# untitled.net
KiCad netlist of a schematic drawn in EAGLE
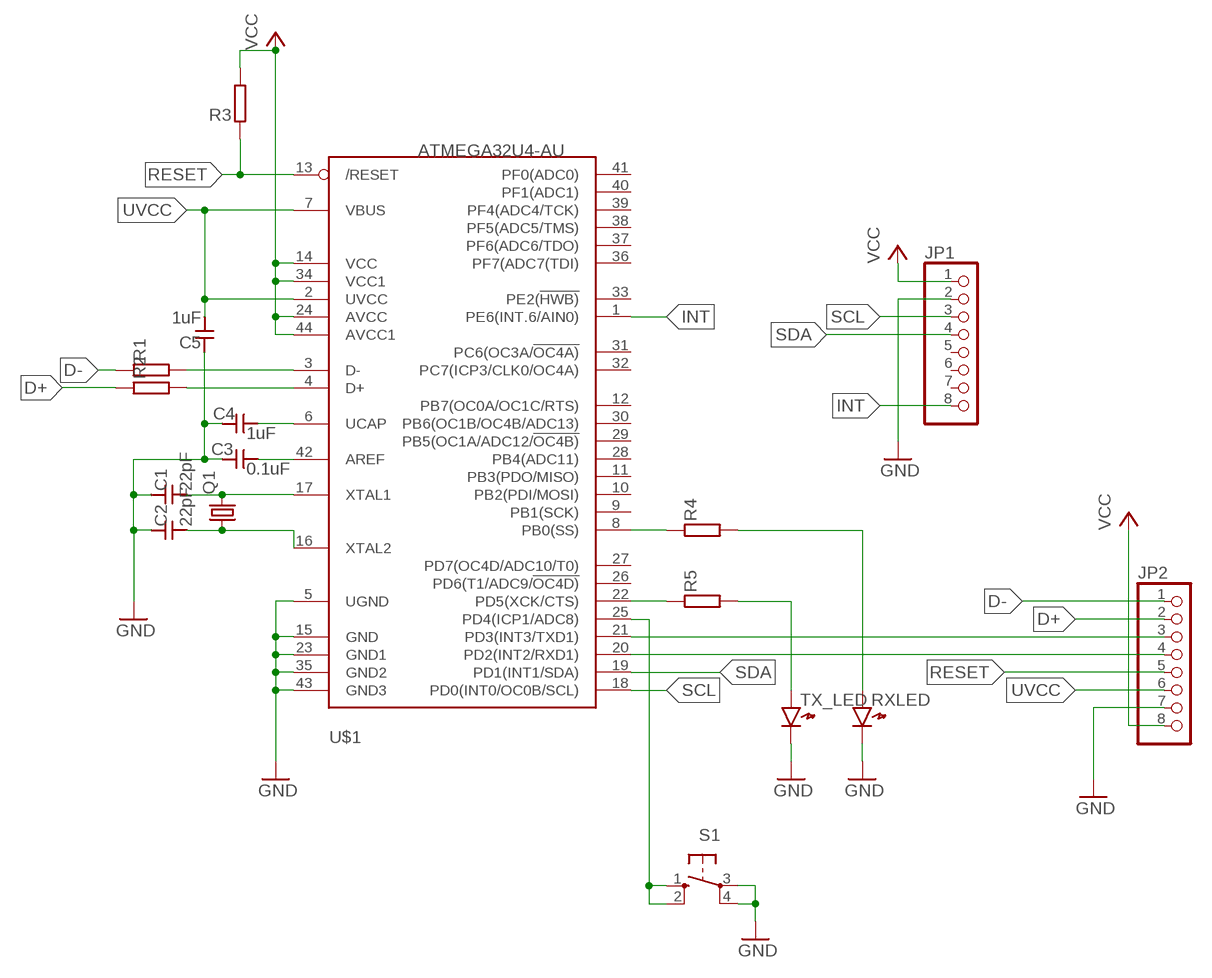
[diagram p0: schematic, sheet 1]

(export (version "E")
  (design (tool "Eeschema 10.0.6"))
  (components
    (comp (ref "C1")
      (value "22pF")
      (footprint "eagle-import:SMD1608")
      (libsource (lib "eagle-import") (part "CAPACITOR1608"))
    )
    (comp (ref "C2")
      (value "22pF")
      (footprint "eagle-import:SMD1608")
      (libsource (lib "eagle-import") (part "CAPACITOR1608"))
    )
    (comp (ref "C3")
      (value "0.1uF")
      (footprint "eagle-import:SMD1608")
      (libsource (lib "eagle-import") (part "CAPACITOR1608"))
    )
    (comp (ref "C4")
      (value "1uF")
      (footprint "eagle-import:SMD1608")
      (libsource (lib "eagle-import") (part "CAPACITOR1608"))
    )
    (comp (ref "C5")
      (value "1uF")
      (footprint "eagle-import:SMD1608")
      (libsource (lib "eagle-import") (part "CAPACITOR1608"))
    )
    (comp (ref "JP1")
      (value "PINHD-1X8")
      (footprint "eagle-import:1X08")
      (libsource (lib "eagle-import") (part "PINHD-1X8"))
    )
    (comp (ref "JP2")
      (value "PINHD-1X8")
      (footprint "eagle-import:1X08")
      (libsource (lib "eagle-import") (part "PINHD-1X8"))
    )
    (comp (ref "Q1")
      (value "CRYSTALHC49S")
      (footprint "eagle-import:HC49_S")
      (libsource (lib "eagle-import") (part "CRYSTALHC49S"))
    )
    (comp (ref "R1")
      (value "RESISTOR1608")
      (footprint "eagle-import:SMD1608")
      (libsource (lib "eagle-import") (part "RESISTOR1608"))
    )
    (comp (ref "R2")
      (value "RESISTOR1608")
      (footprint "eagle-import:SMD1608")
      (libsource (lib "eagle-import") (part "RESISTOR1608"))
    )
    (comp (ref "R3")
      (value "RESISTOR1608")
      (footprint "eagle-import:SMD1608")
      (libsource (lib "eagle-import") (part "RESISTOR1608"))
    )
    (comp (ref "R4")
      (value "RESISTOR1608")
      (footprint "eagle-import:SMD1608")
      (libsource (lib "eagle-import") (part "RESISTOR1608"))
    )
    (comp (ref "R5")
      (value "RESISTOR1608")
      (footprint "eagle-import:SMD1608")
      (libsource (lib "eagle-import") (part "RESISTOR1608"))
    )
    (comp (ref "RXLED")
      (value "LED1608")
      (footprint "eagle-import:LED1608")
      (libsource (lib "eagle-import") (part "LED1608"))
    )
    (comp (ref "S1")
      (value "10-XX")
      (footprint "eagle-import:B3F-10XX")
      (fields (field (name "MPN") "B3F-1000"))
      (libsource (lib "eagle-import") (part "10-XX"))
    )
    (comp (ref "TX_LED")
      (value "LED1608")
      (footprint "eagle-import:LED1608")
      (libsource (lib "eagle-import") (part "LED1608"))
    )
    (comp (ref "U$1")
      (value "ATMEGA32U4-AU")
      (footprint "eagle-import:TQFP44")
      (libsource (lib "eagle-import") (part "ATMEGA32U4-AU"))
    )
  )
  (nets
    (net (code "1") (name "D+") (class "Default")
      (node (ref "JP2") (pin "2") (pinfunction "2_2") (pintype "passive"))
      (node (ref "R2") (pin "1") (pinfunction "1_1") (pintype "passive"))
    )
    (net (code "2") (name "D-") (class "Default")
      (node (ref "JP2") (pin "1") (pinfunction "1_1") (pintype "passive"))
      (node (ref "R1") (pin "1") (pinfunction "1_1") (pintype "passive"))
    )
    (net (code "3") (name "GND") (class "Default")
      (node (ref "C1") (pin "1") (pinfunction "1_1") (pintype "passive"))
      (node (ref "C2") (pin "1") (pinfunction "1_1") (pintype "passive"))
      (node (ref "C3") (pin "1") (pinfunction "1_1") (pintype "passive"))
      (node (ref "C4") (pin "1") (pinfunction "1_1") (pintype "passive"))
      (node (ref "C5") (pin "1") (pinfunction "1_1") (pintype "passive"))
      (node (ref "JP1") (pin "2") (pinfunction "2_2") (pintype "passive"))
      (node (ref "JP2") (pin "7") (pinfunction "7_7") (pintype "passive"))
      (node (ref "RXLED") (pin "K") (pinfunction "K_K") (pintype "passive"))
      (node (ref "S1") (pin "3") (pinfunction "P_3") (pintype "passive"))
      (node (ref "S1") (pin "4") (pinfunction "P1_4") (pintype "passive"))
      (node (ref "TX_LED") (pin "K") (pinfunction "K_K") (pintype "passive"))
      (node (ref "U$1") (pin "15") (pinfunction "GND_15") (pintype "bidirectional"))
      (node (ref "U$1") (pin "23") (pinfunction "GND1_23") (pintype "bidirectional"))
      (node (ref "U$1") (pin "35") (pinfunction "GND2_35") (pintype "bidirectional"))
      (node (ref "U$1") (pin "43") (pinfunction "GND3_43") (pintype "bidirectional"))
      (node (ref "U$1") (pin "5") (pinfunction "UGND_5") (pintype "bidirectional"))
    )
    (net (code "4") (name "INT") (class "Default")
      (node (ref "JP1") (pin "8") (pinfunction "8_8") (pintype "passive"))
      (node (ref "U$1") (pin "1") (pinfunction "PE6(INT.6/AIN0)_1") (pintype "bidirectional"))
    )
    (net (code "5") (name "Net-(R4-Pad2)") (class "Default")
      (node (ref "R4") (pin "2") (pinfunction "2_2") (pintype "passive"))
      (node (ref "RXLED") (pin "A") (pinfunction "A_A") (pintype "passive"))
    )
    (net (code "6") (name "Net-(R5-Pad2)") (class "Default")
      (node (ref "R5") (pin "2") (pinfunction "2_2") (pintype "passive"))
      (node (ref "TX_LED") (pin "A") (pinfunction "A_A") (pintype "passive"))
    )
    (net (code "7") (name "Net-(S1-S)") (class "Default")
      (node (ref "S1") (pin "1") (pinfunction "S_1") (pintype "passive"))
      (node (ref "S1") (pin "2") (pinfunction "S1_2") (pintype "passive"))
      (node (ref "U$1") (pin "25") (pinfunction "PD4(ICP1/ADC8)_25") (pintype "bidirectional"))
    )
    (net (code "8") (name "Net-(U$1-AREF)") (class "Default")
      (node (ref "C3") (pin "2") (pinfunction "2_2") (pintype "passive"))
      (node (ref "U$1") (pin "42") (pinfunction "AREF_42") (pintype "bidirectional"))
    )
    (net (code "9") (name "Net-(U$1-D+)") (class "Default")
      (node (ref "R2") (pin "2") (pinfunction "2_2") (pintype "passive"))
      (node (ref "U$1") (pin "4") (pinfunction "D+_4") (pintype "bidirectional"))
    )
    (net (code "10") (name "Net-(U$1-D-)") (class "Default")
      (node (ref "R1") (pin "2") (pinfunction "2_2") (pintype "passive"))
      (node (ref "U$1") (pin "3") (pinfunction "D-_3") (pintype "bidirectional"))
    )
    (net (code "11") (name "Net-(U$1-PB0(SS))") (class "Default")
      (node (ref "R4") (pin "1") (pinfunction "1_1") (pintype "passive"))
      (node (ref "U$1") (pin "8") (pinfunction "PB0(SS)_8") (pintype "bidirectional"))
    )
    (net (code "12") (name "Net-(U$1-PD2(INT2{slash}RXD1))") (class "Default")
      (node (ref "JP2") (pin "4") (pinfunction "4_4") (pintype "passive"))
      (node (ref "U$1") (pin "20") (pinfunction "PD2(INT2/RXD1)_20") (pintype "bidirectional"))
    )
    (net (code "13") (name "Net-(U$1-PD3(INT3{slash}TXD1))") (class "Default")
      (node (ref "JP2") (pin "3") (pinfunction "3_3") (pintype "passive"))
      (node (ref "U$1") (pin "21") (pinfunction "PD3(INT3/TXD1)_21") (pintype "bidirectional"))
    )
    (net (code "14") (name "Net-(U$1-PD5(XCK{slash}CTS))") (class "Default")
      (node (ref "R5") (pin "1") (pinfunction "1_1") (pintype "passive"))
      (node (ref "U$1") (pin "22") (pinfunction "PD5(XCK/CTS)_22") (pintype "bidirectional"))
    )
    (net (code "15") (name "Net-(U$1-UCAP)") (class "Default")
      (node (ref "C4") (pin "2") (pinfunction "2_2") (pintype "passive"))
      (node (ref "U$1") (pin "6") (pinfunction "UCAP_6") (pintype "bidirectional"))
    )
    (net (code "16") (name "Net-(U$1-XTAL1)") (class "Default")
      (node (ref "C1") (pin "2") (pinfunction "2_2") (pintype "passive"))
      (node (ref "Q1") (pin "2") (pinfunction "2_2") (pintype "passive"))
      (node (ref "U$1") (pin "17") (pinfunction "XTAL1_17") (pintype "bidirectional"))
    )
    (net (code "17") (name "Net-(U$1-XTAL2)") (class "Default")
      (node (ref "C2") (pin "2") (pinfunction "2_2") (pintype "passive"))
      (node (ref "Q1") (pin "1") (pinfunction "1_1") (pintype "passive"))
      (node (ref "U$1") (pin "16") (pinfunction "XTAL2_16") (pintype "bidirectional"))
    )
    (net (code "18") (name "RESET") (class "Default")
      (node (ref "JP2") (pin "5") (pinfunction "5_5") (pintype "passive"))
      (node (ref "R3") (pin "1") (pinfunction "1_1") (pintype "passive"))
      (node (ref "U$1") (pin "13") (pinfunction "/RESET_13") (pintype "bidirectional"))
    )
    (net (code "19") (name "SCL") (class "Default")
      (node (ref "JP1") (pin "3") (pinfunction "3_3") (pintype "passive"))
      (node (ref "U$1") (pin "18") (pinfunction "PD0(INT0/OC0B/SCL)_18") (pintype "bidirectional"))
    )
    (net (code "20") (name "SDA") (class "Default")
      (node (ref "JP1") (pin "4") (pinfunction "4_4") (pintype "passive"))
      (node (ref "U$1") (pin "19") (pinfunction "PD1(INT1/SDA)_19") (pintype "bidirectional"))
    )
    (net (code "21") (name "UVCC") (class "Default")
      (node (ref "C5") (pin "2") (pinfunction "2_2") (pintype "passive"))
      (node (ref "JP2") (pin "6") (pinfunction "6_6") (pintype "passive"))
      (node (ref "U$1") (pin "2") (pinfunction "UVCC_2") (pintype "bidirectional"))
      (node (ref "U$1") (pin "7") (pinfunction "VBUS_7") (pintype "bidirectional"))
    )
    (net (code "22") (name "VCC") (class "Default")
      (node (ref "JP1") (pin "1") (pinfunction "1_1") (pintype "passive"))
      (node (ref "JP2") (pin "8") (pinfunction "8_8") (pintype "passive"))
      (node (ref "R3") (pin "2") (pinfunction "2_2") (pintype "passive"))
      (node (ref "U$1") (pin "14") (pinfunction "VCC_14") (pintype "bidirectional"))
      (node (ref "U$1") (pin "24") (pinfunction "AVCC_24") (pintype "bidirectional"))
      (node (ref "U$1") (pin "34") (pinfunction "VCC1_34") (pintype "bidirectional"))
      (node (ref "U$1") (pin "44") (pinfunction "AVCC1_44") (pintype "bidirectional"))
    )
    (net (code "23") (name "unconnected-(JP1-Pad5)") (class "Default")
      (node (ref "JP1") (pin "5") (pinfunction "5_5") (pintype "passive"))
    )
    (net (code "24") (name "unconnected-(JP1-Pad6)") (class "Default")
      (node (ref "JP1") (pin "6") (pinfunction "6_6") (pintype "passive"))
    )
    (net (code "25") (name "unconnected-(JP1-Pad7)") (class "Default")
      (node (ref "JP1") (pin "7") (pinfunction "7_7") (pintype "passive"))
    )
    (net (code "26") (name "unconnected-(U$1-PB1(SCK)-Pad9)") (class "Default")
      (node (ref "U$1") (pin "9") (pinfunction "PB1(SCK)_9") (pintype "bidirectional"))
    )
    (net (code "27") (name "unconnected-(U$1-PB2(PDI{slash}MOSI)-Pad10)") (class "Default")
      (node (ref "U$1") (pin "10") (pinfunction "PB2(PDI/MOSI)_10") (pintype "bidirectional"))
    )
    (net (code "28") (name "unconnected-(U$1-PB3(PDO{slash}MISO)-Pad11)") (class "Default")
      (node (ref "U$1") (pin "11") (pinfunction "PB3(PDO/MISO)_11") (pintype "bidirectional"))
    )
    (net (code "29") (name "unconnected-(U$1-PB4(ADC11)-Pad28)") (class "Default")
      (node (ref "U$1") (pin "28") (pinfunction "PB4(ADC11)_28") (pintype "bidirectional"))
    )
    (net (code "30") (name "unconnected-(U$1-PB5(OC1A{slash}ADC12{slash}~{OC4B})-Pad29)") (class "Default")
      (node (ref "U$1") (pin "29") (pinfunction "PB5(OC1A/ADC12/~{OC4B})_29") (pintype "bidirectional"))
    )
    (net (code "31") (name "unconnected-(U$1-PB6(OC1B{slash}OC4B{slash}ADC13)-Pad30)") (class "Default")
      (node (ref "U$1") (pin "30") (pinfunction "PB6(OC1B/OC4B/ADC13)_30") (pintype "bidirectional"))
    )
    (net (code "32") (name "unconnected-(U$1-PB7(OC0A{slash}OC1C{slash}RTS)-Pad12)") (class "Default")
      (node (ref "U$1") (pin "12") (pinfunction "PB7(OC0A/OC1C/RTS)_12") (pintype "bidirectional"))
    )
    (net (code "33") (name "unconnected-(U$1-PC6(OC3A{slash}~{OC4A})-Pad31)") (class "Default")
      (node (ref "U$1") (pin "31") (pinfunction "PC6(OC3A/~{OC4A})_31") (pintype "bidirectional"))
    )
    (net (code "34") (name "unconnected-(U$1-PC7(ICP3{slash}CLK0{slash}OC4A)-Pad32)") (class "Default")
      (node (ref "U$1") (pin "32") (pinfunction "PC7(ICP3/CLK0/OC4A)_32") (pintype "bidirectional"))
    )
    (net (code "35") (name "unconnected-(U$1-PD6(T1{slash}ADC9{slash}~{OC4D})-Pad26)") (class "Default")
      (node (ref "U$1") (pin "26") (pinfunction "PD6(T1/ADC9/~{OC4D})_26") (pintype "bidirectional"))
    )
    (net (code "36") (name "unconnected-(U$1-PD7(OC4D{slash}ADC10{slash}T0)-Pad27)") (class "Default")
      (node (ref "U$1") (pin "27") (pinfunction "PD7(OC4D/ADC10/T0)_27") (pintype "bidirectional"))
    )
    (net (code "37") (name "unconnected-(U$1-PE2(~{HWB})-Pad33)") (class "Default")
      (node (ref "U$1") (pin "33") (pinfunction "PE2(~{HWB})_33") (pintype "bidirectional"))
    )
    (net (code "38") (name "unconnected-(U$1-PF0(ADC0)-Pad41)") (class "Default")
      (node (ref "U$1") (pin "41") (pinfunction "PF0(ADC0)_41") (pintype "bidirectional"))
    )
    (net (code "39") (name "unconnected-(U$1-PF1(ADC1)-Pad40)") (class "Default")
      (node (ref "U$1") (pin "40") (pinfunction "PF1(ADC1)_40") (pintype "bidirectional"))
    )
    (net (code "40") (name "unconnected-(U$1-PF4(ADC4{slash}TCK)-Pad39)") (class "Default")
      (node (ref "U$1") (pin "39") (pinfunction "PF4(ADC4/TCK)_39") (pintype "bidirectional"))
    )
    (net (code "41") (name "unconnected-(U$1-PF5(ADC5{slash}TMS)-Pad38)") (class "Default")
      (node (ref "U$1") (pin "38") (pinfunction "PF5(ADC5/TMS)_38") (pintype "bidirectional"))
    )
    (net (code "42") (name "unconnected-(U$1-PF6(ADC6{slash}TDO)-Pad37)") (class "Default")
      (node (ref "U$1") (pin "37") (pinfunction "PF6(ADC6/TDO)_37") (pintype "bidirectional"))
    )
    (net (code "43") (name "unconnected-(U$1-PF7(ADC7(TDI)-Pad36)") (class "Default")
      (node (ref "U$1") (pin "36") (pinfunction "PF7(ADC7(TDI)_36") (pintype "bidirectional"))
    )
  )
)
